# pilpal_final.net
KiCad netlist of a schematic drawn in Altium Designer
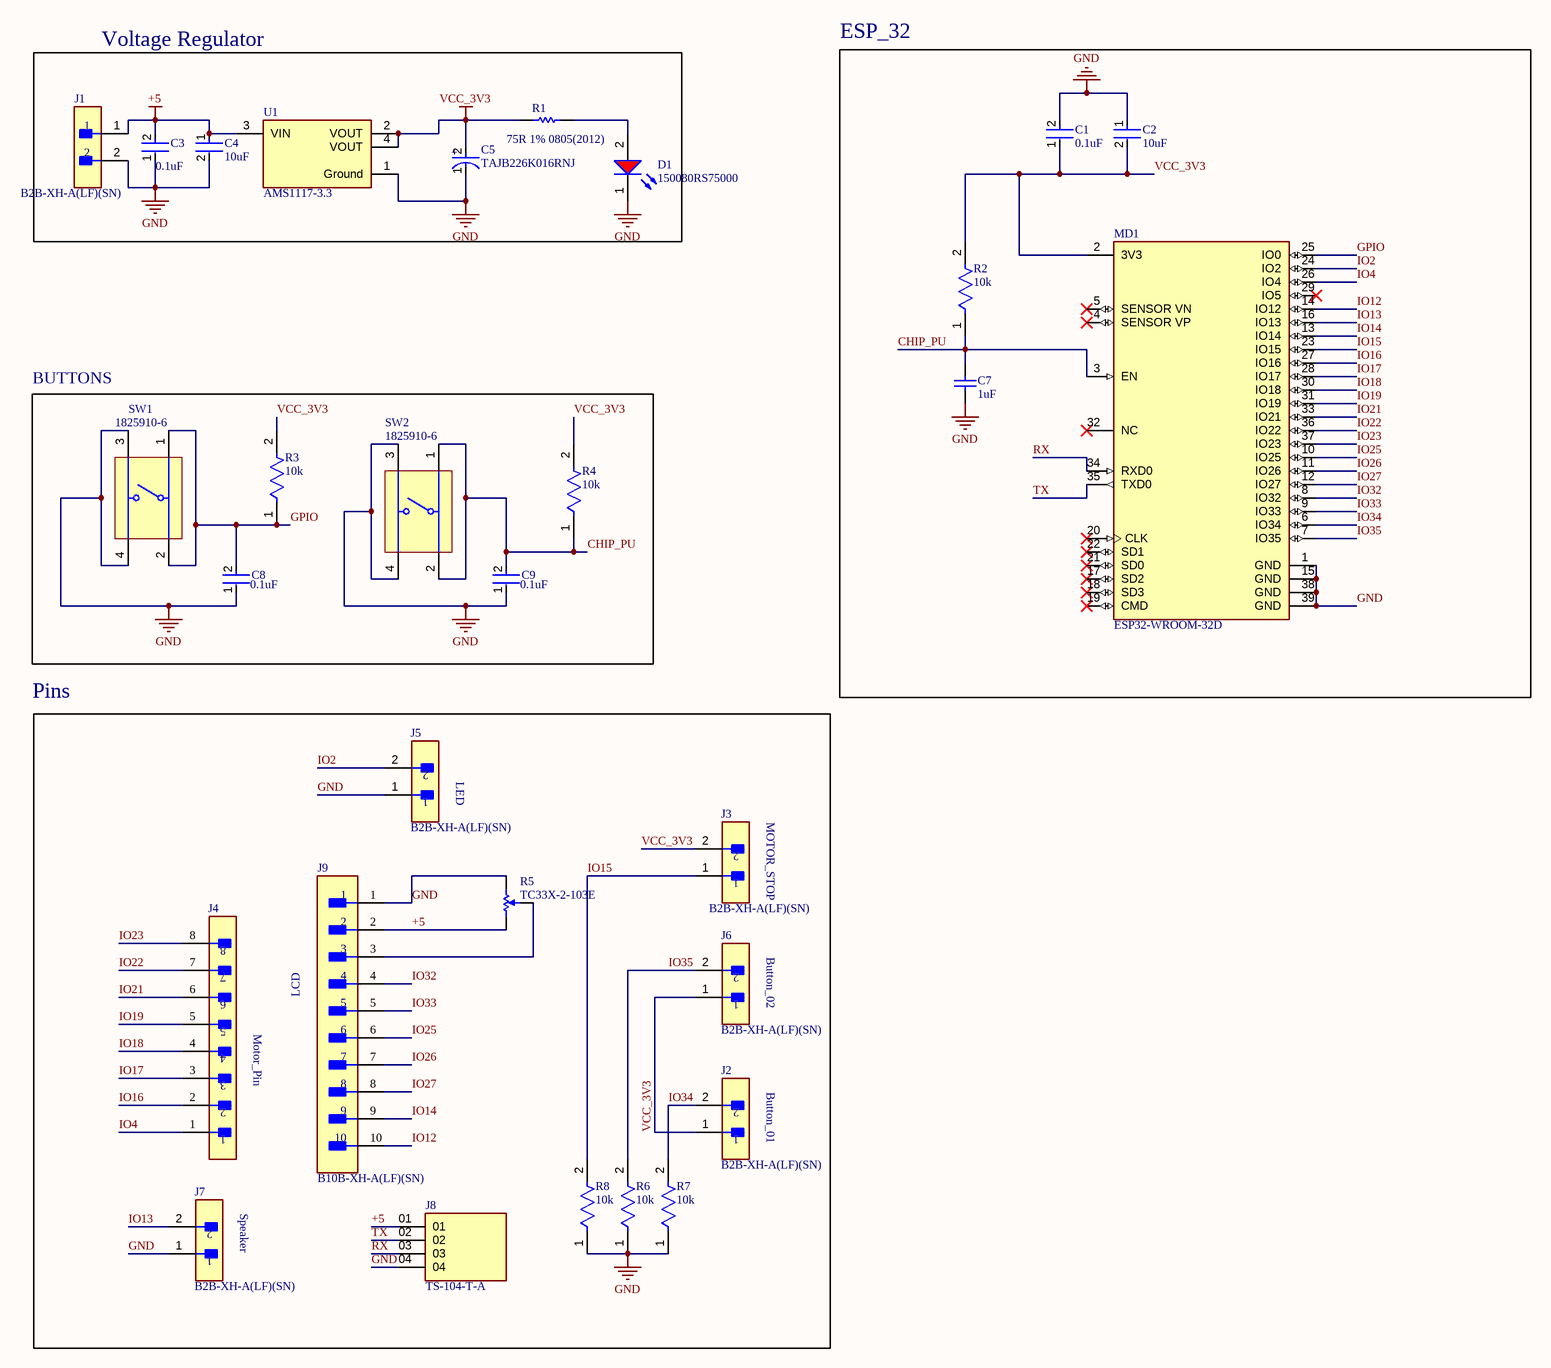
[diagram p0: pilpal_final.SchDoc]

(export (version "E")
  (design (tool "Eeschema 10.0.6"))
  (components
    (comp (ref "C1")
      (value "0.1uF")
      (footprint "FP-GRM15-MFG")
      (description "CAP CER 0.1UF 16V X7R 0402")
      (fields (field (name "MANUFACTURER PART NUMBER") "GRM155R71C104KA88D") (field (name "TOLERANCE") "10%"))
      (libsource (lib "Altium Content Vault") (part "236180d848d6139a670b325ea6854c9"))
    )
    (comp (ref "C2")
      (value "10uF")
      (footprint "FP-GRM188-0_1-e0_2_0_55-IPC_A")
      (description "Chip Multilayer Ceramic Capacitors for General Purpose, 0603, 10uF, X5R, 15%, 20%, 6.3V")
      (fields (field (name "VOLTAGE") "6.3V") (field (name "TOLERANCE") "20%"))
      (libsource (lib "Altium Content Vault") (part "02cd4be3c70576c341d710602a673aa"))
    )
    (comp (ref "C3")
      (value "0.1uF")
      (footprint "FP-GRM15-MFG")
      (description "CAP CER 0.1UF 16V X7R 0402")
      (fields (field (name "MANUFACTURER PART NUMBER") "GRM155R71C104KA88D") (field (name "TOLERANCE") "10%"))
      (libsource (lib "Altium Content Vault") (part "236180d848d6139a670b325ea6854c9"))
    )
    (comp (ref "C4")
      (value "10uF")
      (footprint "FP-GRM188-0_1-e0_2_0_55-IPC_A")
      (description "Chip Multilayer Ceramic Capacitors for General Purpose, 0603, 10uF, X5R, 15%, 20%, 6.3V")
      (fields (field (name "VOLTAGE") "6.3V") (field (name "TOLERANCE") "20%"))
      (libsource (lib "Altium Content Vault") (part "02cd4be3c70576c341d710602a673aa"))
    )
    (comp (ref "C5")
      (value "TAJB226K016RNJ")
      (footprint "FP-TAJB-MFG")
      (description "22uF 16V  ±10% 2.3Ω 1210  SMD Tantalum Capacitor")
      (fields (field (name "VOLTAGE") "16V") (field (name "TOLERANCE") "10%"))
      (libsource (lib "Altium Content Vault") (part "203bc49f2ac43e59fd269a8c329ed05"))
    )
    (comp (ref "C7")
      (value "1uF")
      (footprint "CAPC2013X145X50ML20T25")
      (fields (field (name "PART NUMBER") "C0805C105K9PACTU") (field (name "MANUFACTURER") "Kemet"))
      (libsource (lib "Altium Content Vault") (part "CAP"))
    )
    (comp (ref "C8")
      (value "0.1uF")
      (footprint "FP-GRM15-MFG")
      (description "CAP CER 0.1UF 16V X7R 0402")
      (fields (field (name "MANUFACTURER PART NUMBER") "GRM155R71C104KA88D") (field (name "TOLERANCE") "10%"))
      (libsource (lib "Altium Content Vault") (part "236180d848d6139a670b325ea6854c9"))
    )
    (comp (ref "C9")
      (value "0.1uF")
      (footprint "FP-GRM15-MFG")
      (description "CAP CER 0.1UF 16V X7R 0402")
      (fields (field (name "MANUFACTURER PART NUMBER") "GRM155R71C104KA88D") (field (name "TOLERANCE") "10%"))
      (libsource (lib "Altium Content Vault") (part "236180d848d6139a670b325ea6854c9"))
    )
    (comp (ref "D1")
      (value "150080RS75000")
      (footprint "WL-SMCW_0805_150080xx75000")
      (libsource (lib "Altium Content Vault") (part "LED_Red_2A-1K"))
    )
    (comp (ref "J1")
      (value "B2B-XH-A(LF)(SN)")
      (footprint "FP-B2B-XH-A_LF_SN-MFG")
      (description "CONN HEADER VERT 2POS 2.5MM")
      (libsource (lib "") (part "3bc925449376181038e59eaffc5286c_1"))
    )
    (comp (ref "J2")
      (value "B2B-XH-A(LF)(SN)")
      (footprint "FP-B2B-XH-A_LF_SN-MFG")
      (description "CONN HEADER VERT 2POS 2.5MM")
      (libsource (lib "Altium Content Vault") (part "3bc925449376181038e59eaffc5286c"))
    )
    (comp (ref "J3")
      (value "B2B-XH-A(LF)(SN)")
      (footprint "FP-B2B-XH-A_LF_SN-MFG")
      (description "CONN HEADER VERT 2POS 2.5MM")
      (libsource (lib "Altium Content Vault") (part "3bc925449376181038e59eaffc5286c"))
    )
    (comp (ref "J4")
      (value "B8B-XH-A(LF)(SN)")
      (footprint "FP-B8B-XH-A_LF_SN-MFG")
      (description "CONN HEADER VERT 8POS 2.5MM")
      (libsource (lib "Altium Content Vault") (part "99ec2b232beb5d2356d4d77f6a047f0"))
    )
    (comp (ref "J5")
      (value "B2B-XH-A(LF)(SN)")
      (footprint "FP-B2B-XH-A_LF_SN-MFG")
      (description "CONN HEADER VERT 2POS 2.5MM")
      (libsource (lib "Altium Content Vault") (part "3bc925449376181038e59eaffc5286c"))
    )
    (comp (ref "J6")
      (value "B2B-XH-A(LF)(SN)")
      (footprint "FP-B2B-XH-A_LF_SN-MFG")
      (description "CONN HEADER VERT 2POS 2.5MM")
      (libsource (lib "Altium Content Vault") (part "3bc925449376181038e59eaffc5286c"))
    )
    (comp (ref "J7")
      (value "B2B-XH-A(LF)(SN)")
      (footprint "FP-B2B-XH-A_LF_SN-MFG")
      (description "CONN HEADER VERT 2POS 2.5MM")
      (libsource (lib "Altium Content Vault") (part "3bc925449376181038e59eaffc5286c"))
    )
    (comp (ref "J8")
      (value "TS-104-T-A")
      (footprint "SAMTEC_TS-104-T-A")
      (description "TS - Samtec 2.54mm Single Row Machined Terminal Strip - Fast Stock")
      (fields (field (name "MF") "Samtec Inc."))
      (libsource (lib "TS-104-T-A") (part "TS-104-T-A"))
    )
    (comp (ref "J9")
      (value "B10B-XH-A(LF)(SN)")
      (footprint "FP-B10B-XH-A_LF_SN-MFG")
      (description "CONN HEADER VERT 10POS 2.5MM")
      (libsource (lib "Altium Content Vault") (part "aee40dc8b284c03a16094555aa210be"))
    )
    (comp (ref "MD1")
      (value "ESP32-WROOM-32D")
      (footprint "FP-ESP32-WROOM-32D-MFG")
      (description "WIFI MODULE 32MBITS SPI FLASH")
      (fields
        (field (name "OCTOPART") "https://octopart.com/esp32-wroom-32d-espressif+systems-91040050")
        (field (name "MANUFACTURER") "Espressif Systems")
      )
      (libsource (lib "Altium Content Vault") (part "a031a76f8c27026a7a7f4657ff233a3"))
    )
    (comp (ref "R1")
      (value "75R 1% 0805(2012)")
      (footprint "RESC0805(2012)_M")
      (description "75R 0.125W 1% 0805 (2012 Metric)  SMD")
      (fields (field (name "TOLERANCE") "1 %") (field (name "POWER") "0.125 W"))
      (libsource (lib "Altium Content Vault") (part "RES"))
    )
    (comp (ref "R2")
      (value "10k")
      (footprint "FP-CRG0805-IPC_C")
      (description "RES SMD 10K OHM 1% 1/8W 0805")
      (fields (field (name "TOLERANCE") "1%"))
      (libsource (lib "Altium Content Vault") (part "1029c3af85768c4190bb7ad29bc67b5"))
    )
    (comp (ref "R3")
      (value "10k")
      (footprint "FP-CRG0805-IPC_C")
      (description "RES SMD 10K OHM 1% 1/8W 0805")
      (fields (field (name "TOLERANCE") "1%"))
      (libsource (lib "Altium Content Vault") (part "1029c3af85768c4190bb7ad29bc67b5"))
    )
    (comp (ref "R4")
      (value "10k")
      (footprint "FP-CRG0805-IPC_C")
      (description "RES SMD 10K OHM 1% 1/8W 0805")
      (fields (field (name "TOLERANCE") "1%"))
      (libsource (lib "Altium Content Vault") (part "1029c3af85768c4190bb7ad29bc67b5"))
    )
    (comp (ref "R5")
      (value "TC33X-2-103E")
      (footprint "BOUR-TC33X-2_V")
      (description "Trimming Potentiometer, 10000 Ohm, -40 to 100 degC, 3-Pin SMD, RoHS, Tape and Reel")
      (fields (field (name "TOLERANCE") "25%") (field (name "MANUFACTURER") "Bourns"))
      (libsource (lib "Altium Content Vault") (part "RES-ADJ-3_A"))
    )
    (comp (ref "R6")
      (value "10k")
      (footprint "FP-CRG0805-IPC_C")
      (description "RES SMD 10K OHM 1% 1/8W 0805")
      (fields (field (name "TOLERANCE") "1%"))
      (libsource (lib "Altium Content Vault") (part "1029c3af85768c4190bb7ad29bc67b5"))
    )
    (comp (ref "R7")
      (value "10k")
      (footprint "FP-CRG0805-IPC_C")
      (description "RES SMD 10K OHM 1% 1/8W 0805")
      (fields (field (name "TOLERANCE") "1%"))
      (libsource (lib "Altium Content Vault") (part "1029c3af85768c4190bb7ad29bc67b5"))
    )
    (comp (ref "R8")
      (value "10k")
      (footprint "FP-CRG0805-IPC_C")
      (description "RES SMD 10K OHM 1% 1/8W 0805")
      (fields (field (name "TOLERANCE") "1%"))
      (libsource (lib "Altium Content Vault") (part "1029c3af85768c4190bb7ad29bc67b5"))
    )
    (comp (ref "SW1")
      (value "1825910-6")
      (footprint "TECO-1825910-6_V")
      (description "Tact Switch, SPST-NO, 0.05 A, -35 to 85 degC, 4-Pin THD, RoHS, Bulk")
      (fields (field (name "MANUFACTURER") "TE Connectivity"))
      (libsource (lib "Altium Content Vault") (part "SW-SPST-4_A"))
    )
    (comp (ref "SW2")
      (value "1825910-6")
      (footprint "TECO-1825910-6_V")
      (description "Tact Switch, SPST-NO, 0.05 A, -35 to 85 degC, 4-Pin THD, RoHS, Bulk")
      (fields (field (name "MANUFACTURER") "TE Connectivity"))
      (libsource (lib "Altium Content Vault") (part "SW-SPST-4_A"))
    )
    (comp (ref "U1")
      (value "AMS1117-3.3")
      (footprint "FP-AMS1117-IPC_C")
      (description "LDO Voltage Regulators 1A, 3.3V")
      (fields
        (field (name "OCTOPART") "https://octopart.com/ams1117-3.3-advanced+monolithic+systems-25899300")
        (field (name "MANUFACTURER") "Advanced Monolithic Systems")
      )
      (libsource (lib "Altium Content Vault") (part "8bdbb5f8e77002000e30dd2845d0354"))
    )
  )
  (nets
    (net (code "1") (name "+5") (class "Default")
      (node (ref "C3") (pin "2") (pinfunction "2_2") (pintype "passive"))
      (node (ref "C4") (pin "1") (pinfunction "1_1") (pintype "passive"))
      (node (ref "J1") (pin "1") (pinfunction "1_1") (pintype "passive"))
      (node (ref "J8") (pin "01") (pinfunction "01_01") (pintype "passive"))
      (node (ref "J9") (pin "2") (pinfunction "2_2") (pintype "passive"))
      (node (ref "R5") (pin "1") (pinfunction "1_1") (pintype "passive"))
      (node (ref "U1") (pin "3") (pinfunction "VIN_3") (pintype "power_in"))
    )
    (net (code "2") (name "/CHIP_PU") (class "Default")
      (node (ref "C7") (pin "2") (pinfunction "2_2") (pintype "passive"))
      (node (ref "C9") (pin "2") (pinfunction "2_2") (pintype "passive"))
      (node (ref "MD1") (pin "3") (pinfunction "EN_3") (pintype "input"))
      (node (ref "R2") (pin "1") (pinfunction "1_1") (pintype "passive"))
      (node (ref "R4") (pin "1") (pinfunction "1_1") (pintype "passive"))
      (node (ref "SW2") (pin "1") (pinfunction "1_1") (pintype "passive"))
      (node (ref "SW2") (pin "2") (pinfunction "2_2") (pintype "passive"))
    )
    (net (code "3") (name "/GPIO") (class "Default")
      (node (ref "C8") (pin "2") (pinfunction "2_2") (pintype "passive"))
      (node (ref "MD1") (pin "25") (pinfunction "IO0_25") (pintype "bidirectional"))
      (node (ref "R3") (pin "1") (pinfunction "1_1") (pintype "passive"))
      (node (ref "SW1") (pin "1") (pinfunction "1_1") (pintype "passive"))
      (node (ref "SW1") (pin "2") (pinfunction "2_2") (pintype "passive"))
    )
    (net (code "4") (name "/IO2") (class "Default")
      (node (ref "J5") (pin "2") (pinfunction "2_2") (pintype "passive"))
      (node (ref "MD1") (pin "24") (pinfunction "IO2_24") (pintype "bidirectional"))
    )
    (net (code "5") (name "/IO4") (class "Default")
      (node (ref "J4") (pin "1") (pinfunction "1_1") (pintype "passive"))
      (node (ref "MD1") (pin "26") (pinfunction "IO4_26") (pintype "bidirectional"))
    )
    (net (code "6") (name "/IO12") (class "Default")
      (node (ref "J9") (pin "10") (pinfunction "10_10") (pintype "passive"))
      (node (ref "MD1") (pin "14") (pinfunction "IO12_14") (pintype "bidirectional"))
    )
    (net (code "7") (name "/IO13") (class "Default")
      (node (ref "J7") (pin "2") (pinfunction "2_2") (pintype "passive"))
      (node (ref "MD1") (pin "16") (pinfunction "IO13_16") (pintype "bidirectional"))
    )
    (net (code "8") (name "/IO14") (class "Default")
      (node (ref "J9") (pin "9") (pinfunction "9_9") (pintype "passive"))
      (node (ref "MD1") (pin "13") (pinfunction "IO14_13") (pintype "bidirectional"))
    )
    (net (code "9") (name "/IO15") (class "Default")
      (node (ref "J3") (pin "1") (pinfunction "1_1") (pintype "passive"))
      (node (ref "MD1") (pin "23") (pinfunction "IO15_23") (pintype "bidirectional"))
      (node (ref "R8") (pin "2") (pinfunction "2_2") (pintype "passive"))
    )
    (net (code "10") (name "/IO16") (class "Default")
      (node (ref "J4") (pin "2") (pinfunction "2_2") (pintype "passive"))
      (node (ref "MD1") (pin "27") (pinfunction "IO16_27") (pintype "bidirectional"))
    )
    (net (code "11") (name "/IO17") (class "Default")
      (node (ref "J4") (pin "3") (pinfunction "3_3") (pintype "passive"))
      (node (ref "MD1") (pin "28") (pinfunction "IO17_28") (pintype "bidirectional"))
    )
    (net (code "12") (name "/IO18") (class "Default")
      (node (ref "J4") (pin "4") (pinfunction "4_4") (pintype "passive"))
      (node (ref "MD1") (pin "30") (pinfunction "IO18_30") (pintype "bidirectional"))
    )
    (net (code "13") (name "/IO19") (class "Default")
      (node (ref "J4") (pin "5") (pinfunction "5_5") (pintype "passive"))
      (node (ref "MD1") (pin "31") (pinfunction "IO19_31") (pintype "bidirectional"))
    )
    (net (code "14") (name "/IO21") (class "Default")
      (node (ref "J4") (pin "6") (pinfunction "6_6") (pintype "passive"))
      (node (ref "MD1") (pin "33") (pinfunction "IO21_33") (pintype "bidirectional"))
    )
    (net (code "15") (name "/IO22") (class "Default")
      (node (ref "J4") (pin "7") (pinfunction "7_7") (pintype "passive"))
      (node (ref "MD1") (pin "36") (pinfunction "IO22_36") (pintype "bidirectional"))
    )
    (net (code "16") (name "/IO23") (class "Default")
      (node (ref "J4") (pin "8") (pinfunction "8_8") (pintype "passive"))
      (node (ref "MD1") (pin "37") (pinfunction "IO23_37") (pintype "bidirectional"))
    )
    (net (code "17") (name "/IO25") (class "Default")
      (node (ref "J9") (pin "6") (pinfunction "6_6") (pintype "passive"))
      (node (ref "MD1") (pin "10") (pinfunction "IO25_10") (pintype "bidirectional"))
    )
    (net (code "18") (name "/IO26") (class "Default")
      (node (ref "J9") (pin "7") (pinfunction "7_7") (pintype "passive"))
      (node (ref "MD1") (pin "11") (pinfunction "IO26_11") (pintype "bidirectional"))
    )
    (net (code "19") (name "/IO27") (class "Default")
      (node (ref "J9") (pin "8") (pinfunction "8_8") (pintype "passive"))
      (node (ref "MD1") (pin "12") (pinfunction "IO27_12") (pintype "bidirectional"))
    )
    (net (code "20") (name "/IO32") (class "Default")
      (node (ref "J9") (pin "4") (pinfunction "4_4") (pintype "passive"))
      (node (ref "MD1") (pin "8") (pinfunction "IO32_8") (pintype "bidirectional"))
    )
    (net (code "21") (name "/IO33") (class "Default")
      (node (ref "J9") (pin "5") (pinfunction "5_5") (pintype "passive"))
      (node (ref "MD1") (pin "9") (pinfunction "IO33_9") (pintype "bidirectional"))
    )
    (net (code "22") (name "/IO34") (class "Default")
      (node (ref "J2") (pin "2") (pinfunction "2_2") (pintype "passive"))
      (node (ref "MD1") (pin "6") (pinfunction "IO34_6") (pintype "bidirectional"))
      (node (ref "R7") (pin "2") (pinfunction "2_2") (pintype "passive"))
    )
    (net (code "23") (name "/IO35") (class "Default")
      (node (ref "J6") (pin "2") (pinfunction "2_2") (pintype "passive"))
      (node (ref "MD1") (pin "7") (pinfunction "IO35_7") (pintype "bidirectional"))
      (node (ref "R6") (pin "2") (pinfunction "2_2") (pintype "passive"))
    )
    (net (code "24") (name "/RX") (class "Default")
      (node (ref "J8") (pin "03") (pinfunction "03_03") (pintype "passive"))
      (node (ref "MD1") (pin "34") (pinfunction "RXD0_34") (pintype "input"))
    )
    (net (code "25") (name "/TX") (class "Default")
      (node (ref "J8") (pin "02") (pinfunction "02_02") (pintype "passive"))
      (node (ref "MD1") (pin "35") (pinfunction "TXD0_35") (pintype "output"))
    )
    (net (code "26") (name "GND") (class "Default")
      (node (ref "C1") (pin "2") (pinfunction "2_2") (pintype "passive"))
      (node (ref "C2") (pin "1") (pinfunction "1_1") (pintype "passive"))
      (node (ref "C3") (pin "1") (pinfunction "1_1") (pintype "passive"))
      (node (ref "C4") (pin "2") (pinfunction "2_2") (pintype "passive"))
      (node (ref "C5") (pin "1") (pinfunction "C_1") (pintype "passive"))
      (node (ref "C7") (pin "1") (pinfunction "1_1") (pintype "passive"))
      (node (ref "C8") (pin "1") (pinfunction "1_1") (pintype "passive"))
      (node (ref "C9") (pin "1") (pinfunction "1_1") (pintype "passive"))
      (node (ref "D1") (pin "1") (pinfunction "K_1") (pintype "passive"))
      (node (ref "J1") (pin "2") (pinfunction "2_2") (pintype "passive"))
      (node (ref "J5") (pin "1") (pinfunction "1_1") (pintype "passive"))
      (node (ref "J7") (pin "1") (pinfunction "1_1") (pintype "passive"))
      (node (ref "J8") (pin "04") (pinfunction "04_04") (pintype "passive"))
      (node (ref "J9") (pin "1") (pinfunction "1_1") (pintype "passive"))
      (node (ref "MD1") (pin "1") (pinfunction "GND_1") (pintype "power_in"))
      (node (ref "MD1") (pin "15") (pinfunction "GND_15") (pintype "power_in"))
      (node (ref "MD1") (pin "38") (pinfunction "GND_38") (pintype "power_in"))
      (node (ref "MD1") (pin "39") (pinfunction "GND_39") (pintype "power_in"))
      (node (ref "R5") (pin "3") (pinfunction "3_3") (pintype "passive"))
      (node (ref "R6") (pin "1") (pinfunction "1_1") (pintype "passive"))
      (node (ref "R7") (pin "1") (pinfunction "1_1") (pintype "passive"))
      (node (ref "R8") (pin "1") (pinfunction "1_1") (pintype "passive"))
      (node (ref "SW1") (pin "3") (pinfunction "3_3") (pintype "passive"))
      (node (ref "SW1") (pin "4") (pinfunction "4_4") (pintype "passive"))
      (node (ref "SW2") (pin "3") (pinfunction "3_3") (pintype "passive"))
      (node (ref "SW2") (pin "4") (pinfunction "4_4") (pintype "passive"))
      (node (ref "U1") (pin "1") (pinfunction "Ground_1") (pintype "power_in"))
    )
    (net (code "27") (name "Net-(D1-A)") (class "Default")
      (node (ref "D1") (pin "2") (pinfunction "A_2") (pintype "passive"))
      (node (ref "R1") (pin "2") (pinfunction "2_2") (pintype "passive"))
    )
    (net (code "28") (name "Net-(J9-Pad3)") (class "Default")
      (node (ref "J9") (pin "3") (pinfunction "3_3") (pintype "passive"))
      (node (ref "R5") (pin "2") (pinfunction "2_2") (pintype "passive"))
    )
    (net (code "29") (name "VCC_3V3") (class "Default")
      (node (ref "C1") (pin "1") (pinfunction "1_1") (pintype "passive"))
      (node (ref "C2") (pin "2") (pinfunction "2_2") (pintype "passive"))
      (node (ref "C5") (pin "2") (pinfunction "A_2") (pintype "passive"))
      (node (ref "J2") (pin "1") (pinfunction "1_1") (pintype "passive"))
      (node (ref "J3") (pin "2") (pinfunction "2_2") (pintype "passive"))
      (node (ref "J6") (pin "1") (pinfunction "1_1") (pintype "passive"))
      (node (ref "MD1") (pin "2") (pinfunction "3V3_2") (pintype "power_in"))
      (node (ref "R1") (pin "1") (pinfunction "1_1") (pintype "passive"))
      (node (ref "R2") (pin "2") (pinfunction "2_2") (pintype "passive"))
      (node (ref "R3") (pin "2") (pinfunction "2_2") (pintype "passive"))
      (node (ref "R4") (pin "2") (pinfunction "2_2") (pintype "passive"))
      (node (ref "U1") (pin "2") (pinfunction "VOUT_2") (pintype "passive"))
      (node (ref "U1") (pin "4") (pinfunction "VOUT_4") (pintype "passive"))
    )
    (net (code "30") (name "unconnected-(MD1-CLK-Pad20)") (class "Default")
      (node (ref "MD1") (pin "20") (pinfunction "CLK_20") (pintype "input+no_connect"))
    )
    (net (code "31") (name "unconnected-(MD1-CMD-Pad19)") (class "Default")
      (node (ref "MD1") (pin "19") (pinfunction "CMD_19") (pintype "bidirectional+no_connect"))
    )
    (net (code "32") (name "unconnected-(MD1-IO5-Pad29)") (class "Default")
      (node (ref "MD1") (pin "29") (pinfunction "IO5_29") (pintype "bidirectional+no_connect"))
    )
    (net (code "33") (name "unconnected-(MD1-NC-Pad32)") (class "Default")
      (node (ref "MD1") (pin "32") (pinfunction "NC_32") (pintype "passive+no_connect"))
    )
    (net (code "34") (name "unconnected-(MD1-SD0-Pad21)") (class "Default")
      (node (ref "MD1") (pin "21") (pinfunction "SD0_21") (pintype "bidirectional+no_connect"))
    )
    (net (code "35") (name "unconnected-(MD1-SD1-Pad22)") (class "Default")
      (node (ref "MD1") (pin "22") (pinfunction "SD1_22") (pintype "bidirectional+no_connect"))
    )
    (net (code "36") (name "unconnected-(MD1-SD2-Pad17)") (class "Default")
      (node (ref "MD1") (pin "17") (pinfunction "SD2_17") (pintype "bidirectional+no_connect"))
    )
    (net (code "37") (name "unconnected-(MD1-SD3-Pad18)") (class "Default")
      (node (ref "MD1") (pin "18") (pinfunction "SD3_18") (pintype "bidirectional+no_connect"))
    )
    (net (code "38") (name "unconnected-(MD1-SENSOR_VN-Pad5)") (class "Default")
      (node (ref "MD1") (pin "5") (pinfunction "SENSOR_VN_5") (pintype "bidirectional+no_connect"))
    )
    (net (code "39") (name "unconnected-(MD1-SENSOR_VP-Pad4)") (class "Default")
      (node (ref "MD1") (pin "4") (pinfunction "SENSOR_VP_4") (pintype "bidirectional+no_connect"))
    )
  )
)
